# SparkFun_Polar-HeartRate.net
KiCad netlist of a schematic drawn in EAGLE
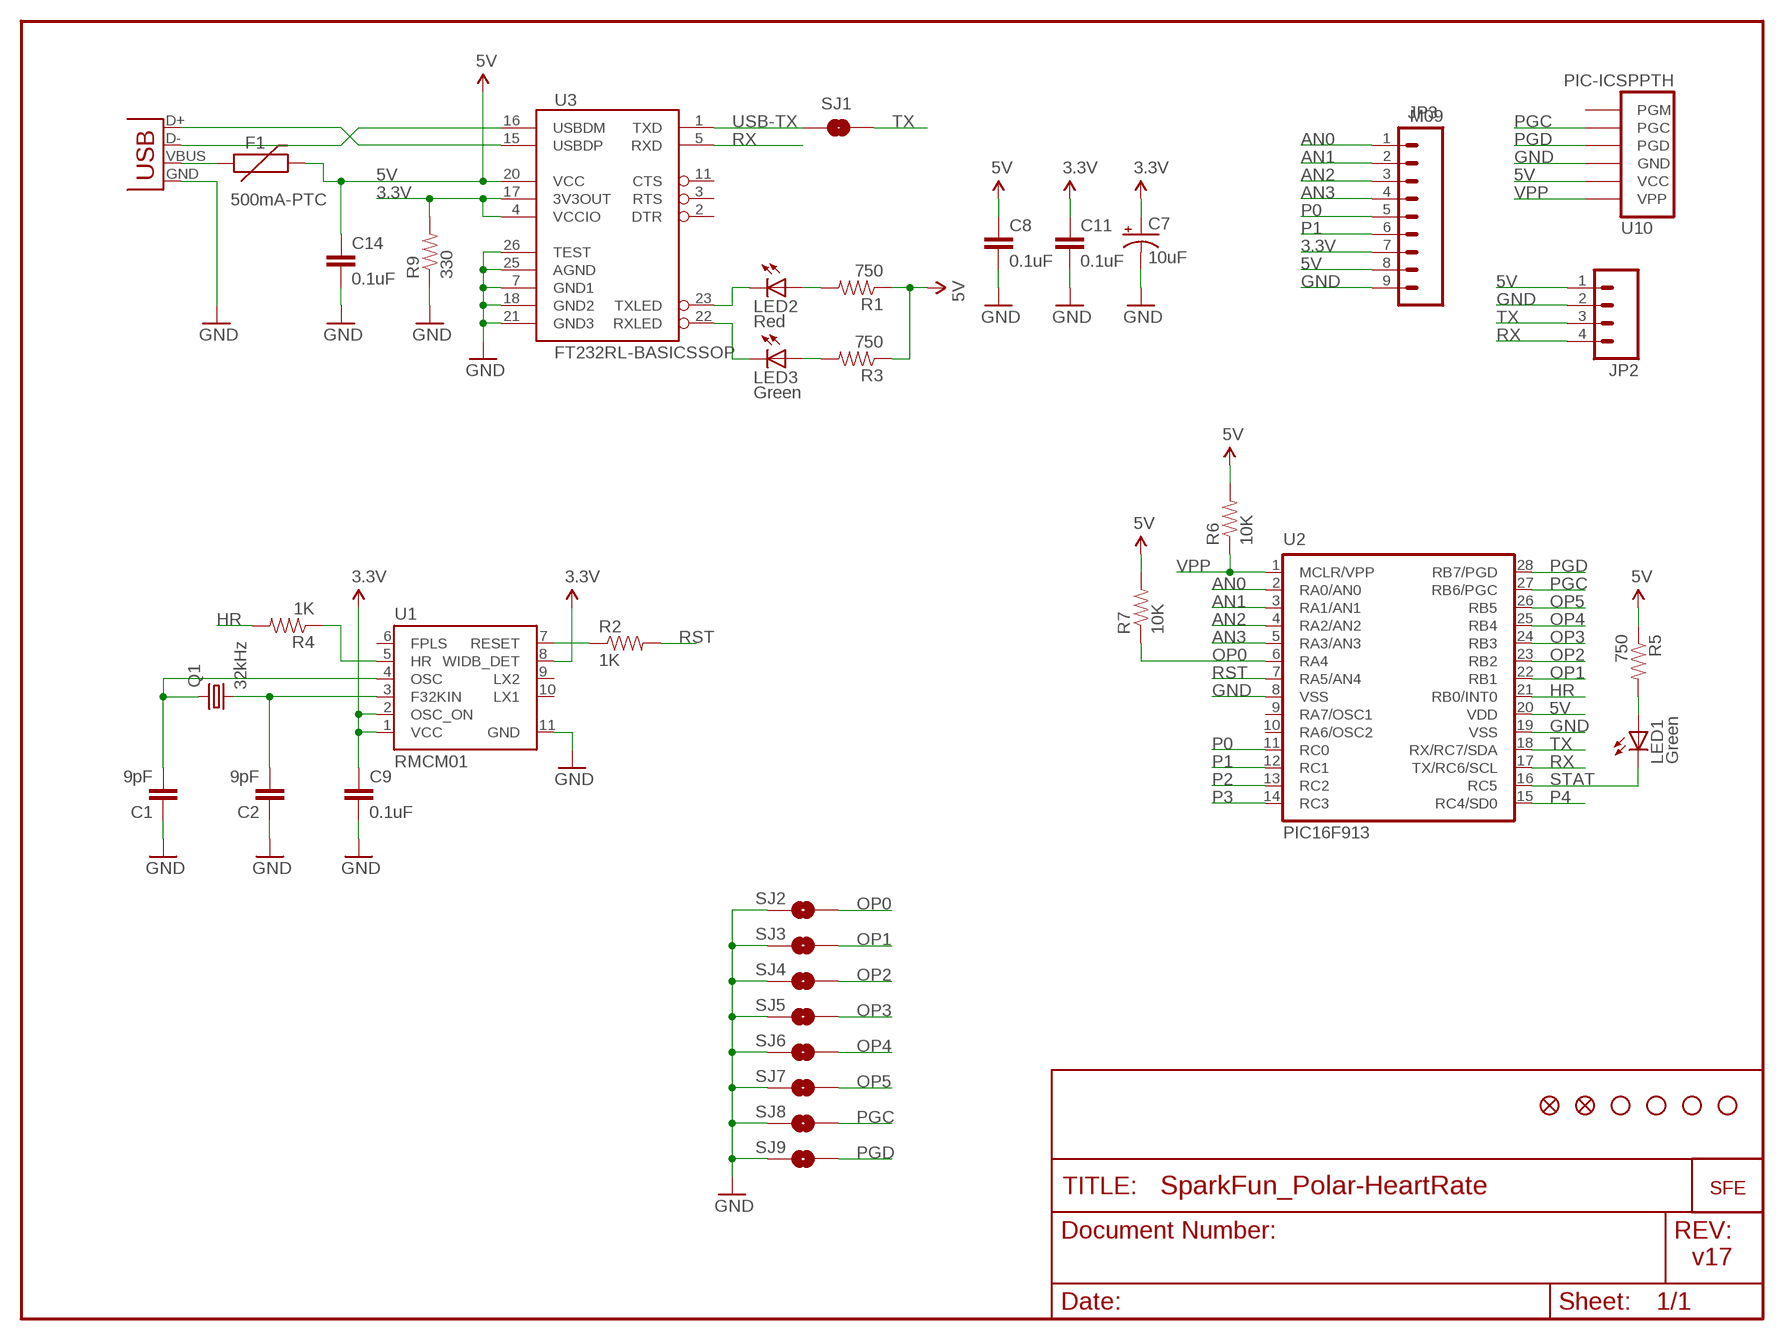
[diagram p0: schematic, sheet 1]

(export (version "E")
  (design (tool "Eeschema 10.0.6"))
  (components
    (comp (ref "C1")
      (value "9pF")
      (footprint "eagle-import:0402-CAP")
      (libsource (lib "eagle-import") (part "CAP0402-CAP"))
    )
    (comp (ref "C2")
      (value "9pF")
      (footprint "eagle-import:0402-CAP")
      (libsource (lib "eagle-import") (part "CAP0402-CAP"))
    )
    (comp (ref "C7")
      (value "10uF")
      (footprint "eagle-import:EIA3216")
      (libsource (lib "eagle-import") (part "CAP_POL1206"))
    )
    (comp (ref "C8")
      (value "0.1uF")
      (footprint "eagle-import:0402-CAP")
      (libsource (lib "eagle-import") (part "CAP0402-CAP"))
    )
    (comp (ref "C9")
      (value "0.1uF")
      (footprint "eagle-import:0402-CAP")
      (libsource (lib "eagle-import") (part "CAP0402-CAP"))
    )
    (comp (ref "C11")
      (value "0.1uF")
      (footprint "eagle-import:0402-CAP")
      (libsource (lib "eagle-import") (part "CAP0402-CAP"))
    )
    (comp (ref "C14")
      (value "0.1uF")
      (footprint "eagle-import:0402-CAP")
      (libsource (lib "eagle-import") (part "CAP0402-CAP"))
    )
    (comp (ref "F1")
      (value "500mA-PTC")
      (footprint "eagle-import:PTC-1206")
      (libsource (lib "eagle-import") (part "PTCSMD"))
    )
    (comp (ref "JP2")
      (value "M04PTH")
      (footprint "eagle-import:1X04")
      (libsource (lib "eagle-import") (part "M04PTH"))
    )
    (comp (ref "JP3")
      (value "M09")
      (footprint "eagle-import:1X09")
      (libsource (lib "eagle-import") (part "M09"))
    )
    (comp (ref "LED1")
      (value "Green")
      (footprint "eagle-import:LED-0603")
      (libsource (lib "eagle-import") (part "LED0603"))
    )
    (comp (ref "LED2")
      (value "Red")
      (footprint "eagle-import:LED-0603")
      (libsource (lib "eagle-import") (part "LED0603"))
    )
    (comp (ref "LED3")
      (value "Green")
      (footprint "eagle-import:LED-0603")
      (libsource (lib "eagle-import") (part "LED0603"))
    )
    (comp (ref "Q1")
      (value "32kHz")
      (footprint "eagle-import:CRYSTAL-32KHZ-SMD_EPSON_MC146")
      (libsource (lib "eagle-import") (part "CRYSTALEPSONMC146"))
    )
    (comp (ref "R1")
      (value "750")
      (footprint "eagle-import:0402-RES")
      (libsource (lib "eagle-import") (part "RESISTOR0402-RES"))
    )
    (comp (ref "R2")
      (value "1K")
      (footprint "eagle-import:0402-RES")
      (libsource (lib "eagle-import") (part "RESISTOR0402-RES"))
    )
    (comp (ref "R3")
      (value "750")
      (footprint "eagle-import:0402-RES")
      (libsource (lib "eagle-import") (part "RESISTOR0402-RES"))
    )
    (comp (ref "R4")
      (value "1K")
      (footprint "eagle-import:0402-RES")
      (libsource (lib "eagle-import") (part "RESISTOR0402-RES"))
    )
    (comp (ref "R5")
      (value "750")
      (footprint "eagle-import:0402-RES")
      (libsource (lib "eagle-import") (part "RESISTOR0402-RES"))
    )
    (comp (ref "R6")
      (value "10K")
      (footprint "eagle-import:0402-RES")
      (libsource (lib "eagle-import") (part "RESISTOR0402-RES"))
    )
    (comp (ref "R7")
      (value "10K")
      (footprint "eagle-import:0402-RES")
      (libsource (lib "eagle-import") (part "RESISTOR0402-RES"))
    )
    (comp (ref "R9")
      (value "330")
      (footprint "eagle-import:0402-RES")
      (libsource (lib "eagle-import") (part "RESISTOR0402-RES"))
    )
    (comp (ref "SJ1")
      (value "SOLDERJUMPERNC2")
      (footprint "eagle-import:SJ_2S-NOTRACE")
      (libsource (lib "eagle-import") (part "SOLDERJUMPERNC2"))
    )
    (comp (ref "SJ2")
      (value "SOLDERJUMPERNO")
      (footprint "eagle-import:SJ_2S-NO")
      (libsource (lib "eagle-import") (part "SOLDERJUMPERNO"))
    )
    (comp (ref "SJ3")
      (value "SOLDERJUMPERNO")
      (footprint "eagle-import:SJ_2S-NO")
      (libsource (lib "eagle-import") (part "SOLDERJUMPERNO"))
    )
    (comp (ref "SJ4")
      (value "SOLDERJUMPERNO")
      (footprint "eagle-import:SJ_2S-NO")
      (libsource (lib "eagle-import") (part "SOLDERJUMPERNO"))
    )
    (comp (ref "SJ5")
      (value "SOLDERJUMPERNO")
      (footprint "eagle-import:SJ_2S-NO")
      (libsource (lib "eagle-import") (part "SOLDERJUMPERNO"))
    )
    (comp (ref "SJ6")
      (value "SOLDERJUMPERNO")
      (footprint "eagle-import:SJ_2S-NO")
      (libsource (lib "eagle-import") (part "SOLDERJUMPERNO"))
    )
    (comp (ref "SJ7")
      (value "SOLDERJUMPERNO")
      (footprint "eagle-import:SJ_2S-NO")
      (libsource (lib "eagle-import") (part "SOLDERJUMPERNO"))
    )
    (comp (ref "SJ8")
      (value "SOLDERJUMPERNO")
      (footprint "eagle-import:SJ_2S-NO")
      (libsource (lib "eagle-import") (part "SOLDERJUMPERNO"))
    )
    (comp (ref "SJ9")
      (value "SOLDERJUMPERNO")
      (footprint "eagle-import:SJ_2S-NO")
      (libsource (lib "eagle-import") (part "SOLDERJUMPERNO"))
    )
    (comp (ref "U$1")
      (value "LOGO-SFENEW")
      (footprint "eagle-import:SFE-NEW-WEBLOGO")
      (libsource (lib "eagle-import") (part "LOGO-SFENEW"))
    )
    (comp (ref "U$4")
      (value "FIDUCIAL1X2")
      (footprint "eagle-import:FIDUCIAL-1X2")
      (libsource (lib "eagle-import") (part "FIDUCIAL1X2"))
    )
    (comp (ref "U$8")
      (value "FIDUCIAL1X2")
      (footprint "eagle-import:FIDUCIAL-1X2")
      (libsource (lib "eagle-import") (part "FIDUCIAL1X2"))
    )
    (comp (ref "U$13")
      (value "STAND-OFF")
      (footprint "eagle-import:STAND-OFF")
      (libsource (lib "eagle-import") (part "STAND-OFF"))
    )
    (comp (ref "U$15")
      (value "STAND-OFF")
      (footprint "eagle-import:STAND-OFF")
      (libsource (lib "eagle-import") (part "STAND-OFF"))
    )
    (comp (ref "U$16")
      (value "STAND-OFF")
      (footprint "eagle-import:STAND-OFF")
      (libsource (lib "eagle-import") (part "STAND-OFF"))
    )
    (comp (ref "U$17")
      (value "STAND-OFF")
      (footprint "eagle-import:STAND-OFF")
      (libsource (lib "eagle-import") (part "STAND-OFF"))
    )
    (comp (ref "U1")
      (value "RMCM01")
      (footprint "eagle-import:RMCM01")
      (libsource (lib "eagle-import") (part "RMCM01SMD"))
    )
    (comp (ref "U2")
      (value "PIC16F913")
      (footprint "eagle-import:SO-28W")
      (libsource (lib "eagle-import") (part "PIC16F913SOIC28"))
    )
    (comp (ref "U3")
      (value "FT232RL-BASICSSOP")
      (footprint "eagle-import:SSOP28DB")
      (libsource (lib "eagle-import") (part "FT232RL-BASICSSOP"))
    )
    (comp (ref "U10")
      (value "PIC-ICSPPTH")
      (footprint "eagle-import:MOLEX-1X6")
      (libsource (lib "eagle-import") (part "PIC-ICSPPTH"))
    )
    (comp (ref "X1")
      (value "USBSMD")
      (footprint "eagle-import:USB-MINIB")
      (libsource (lib "eagle-import") (part "USBSMD"))
    )
  )
  (nets
    (net (code "1") (name "/AN0") (class "Default")
      (node (ref "JP3") (pin "1") (pinfunction "1_1") (pintype "passive"))
      (node (ref "U2") (pin "2") (pinfunction "RA0/AN0_2") (pintype "bidirectional"))
    )
    (net (code "2") (name "/AN1") (class "Default")
      (node (ref "JP3") (pin "2") (pinfunction "2_2") (pintype "passive"))
      (node (ref "U2") (pin "3") (pinfunction "RA1/AN1_3") (pintype "bidirectional"))
    )
    (net (code "3") (name "/AN2") (class "Default")
      (node (ref "JP3") (pin "3") (pinfunction "3_3") (pintype "passive"))
      (node (ref "U2") (pin "4") (pinfunction "RA2/AN2_4") (pintype "bidirectional"))
    )
    (net (code "4") (name "/AN3") (class "Default")
      (node (ref "JP3") (pin "4") (pinfunction "4_4") (pintype "passive"))
      (node (ref "U2") (pin "5") (pinfunction "RA3/AN3_5") (pintype "bidirectional"))
    )
    (net (code "5") (name "/HR") (class "Default")
      (node (ref "R4") (pin "2") (pinfunction "2_2") (pintype "passive"))
      (node (ref "U2") (pin "21") (pinfunction "RB0/INT0_21") (pintype "bidirectional"))
    )
    (net (code "6") (name "/OP0") (class "Default")
      (node (ref "R7") (pin "1") (pinfunction "1_1") (pintype "passive"))
      (node (ref "SJ2") (pin "2") (pinfunction "2_2") (pintype "passive"))
      (node (ref "U2") (pin "6") (pinfunction "RA4_6") (pintype "bidirectional"))
    )
    (net (code "7") (name "/OP1") (class "Default")
      (node (ref "SJ3") (pin "2") (pinfunction "2_2") (pintype "passive"))
      (node (ref "U2") (pin "22") (pinfunction "RB1_22") (pintype "bidirectional"))
    )
    (net (code "8") (name "/OP2") (class "Default")
      (node (ref "SJ4") (pin "2") (pinfunction "2_2") (pintype "passive"))
      (node (ref "U2") (pin "23") (pinfunction "RB2_23") (pintype "bidirectional"))
    )
    (net (code "9") (name "/OP3") (class "Default")
      (node (ref "SJ5") (pin "2") (pinfunction "2_2") (pintype "passive"))
      (node (ref "U2") (pin "24") (pinfunction "RB3_24") (pintype "bidirectional"))
    )
    (net (code "10") (name "/OP4") (class "Default")
      (node (ref "SJ6") (pin "2") (pinfunction "2_2") (pintype "passive"))
      (node (ref "U2") (pin "25") (pinfunction "RB4_25") (pintype "bidirectional"))
    )
    (net (code "11") (name "/OP5") (class "Default")
      (node (ref "SJ7") (pin "2") (pinfunction "2_2") (pintype "passive"))
      (node (ref "U2") (pin "26") (pinfunction "RB5_26") (pintype "bidirectional"))
    )
    (net (code "12") (name "/P0") (class "Default")
      (node (ref "JP3") (pin "5") (pinfunction "5_5") (pintype "passive"))
      (node (ref "U2") (pin "11") (pinfunction "RC0_11") (pintype "bidirectional"))
    )
    (net (code "13") (name "/P1") (class "Default")
      (node (ref "JP3") (pin "6") (pinfunction "6_6") (pintype "passive"))
      (node (ref "U2") (pin "12") (pinfunction "RC1_12") (pintype "bidirectional"))
    )
    (net (code "14") (name "/P2") (class "Default")
      (node (ref "U2") (pin "13") (pinfunction "RC2_13") (pintype "bidirectional"))
    )
    (net (code "15") (name "/P3") (class "Default")
      (node (ref "U2") (pin "14") (pinfunction "RC3_14") (pintype "bidirectional"))
    )
    (net (code "16") (name "/P4") (class "Default")
      (node (ref "U2") (pin "15") (pinfunction "RC4/SD0_15") (pintype "bidirectional"))
    )
    (net (code "17") (name "/PGC") (class "Default")
      (node (ref "SJ8") (pin "2") (pinfunction "2_2") (pintype "passive"))
      (node (ref "U10") (pin "2") (pinfunction "PGC_2") (pintype "bidirectional"))
      (node (ref "U2") (pin "27") (pinfunction "RB6/PGC_27") (pintype "bidirectional"))
    )
    (net (code "18") (name "/PGD") (class "Default")
      (node (ref "SJ9") (pin "2") (pinfunction "2_2") (pintype "passive"))
      (node (ref "U10") (pin "3") (pinfunction "PGD_3") (pintype "bidirectional"))
      (node (ref "U2") (pin "28") (pinfunction "RB7/PGD_28") (pintype "bidirectional"))
    )
    (net (code "19") (name "/RST") (class "Default")
      (node (ref "R2") (pin "2") (pinfunction "2_2") (pintype "passive"))
      (node (ref "U2") (pin "7") (pinfunction "RA5/AN4_7") (pintype "bidirectional"))
    )
    (net (code "20") (name "/RX") (class "Default")
      (node (ref "JP2") (pin "4") (pinfunction "4_4") (pintype "passive"))
      (node (ref "U2") (pin "17") (pinfunction "TX/RC6/SCL_17") (pintype "bidirectional"))
      (node (ref "U3") (pin "5") (pinfunction "RXD_5") (pintype "input"))
    )
    (net (code "21") (name "/STAT") (class "Default")
      (node (ref "LED1") (pin "C") (pinfunction "C_C") (pintype "passive"))
      (node (ref "U2") (pin "16") (pinfunction "RC5_16") (pintype "bidirectional"))
    )
    (net (code "22") (name "/TX") (class "Default")
      (node (ref "JP2") (pin "3") (pinfunction "3_3") (pintype "passive"))
      (node (ref "SJ1") (pin "2") (pinfunction "2_2") (pintype "passive"))
      (node (ref "U2") (pin "18") (pinfunction "RX/RC7/SDA_18") (pintype "input"))
    )
    (net (code "23") (name "/USB-TX") (class "Default")
      (node (ref "SJ1") (pin "1") (pinfunction "1_1") (pintype "passive"))
      (node (ref "U3") (pin "1") (pinfunction "TXD_1") (pintype "output"))
    )
    (net (code "24") (name "/VPP") (class "Default")
      (node (ref "R6") (pin "1") (pinfunction "1_1") (pintype "passive"))
      (node (ref "U10") (pin "6") (pinfunction "VPP_6") (pintype "bidirectional"))
      (node (ref "U2") (pin "1") (pinfunction "MCLR/VPP_1") (pintype "bidirectional"))
    )
    (net (code "25") (name "3.3V") (class "Default")
      (node (ref "C11") (pin "1") (pinfunction "1_1") (pintype "passive"))
      (node (ref "C7") (pin "A") (pinfunction "+_A") (pintype "passive"))
      (node (ref "C9") (pin "1") (pinfunction "1_1") (pintype "passive"))
      (node (ref "JP3") (pin "7") (pinfunction "7_7") (pintype "passive"))
      (node (ref "R9") (pin "2") (pinfunction "2_2") (pintype "passive"))
      (node (ref "U1") (pin "1") (pinfunction "VCC_1") (pintype "bidirectional"))
      (node (ref "U1") (pin "2") (pinfunction "OSC_ON_2") (pintype "bidirectional"))
      (node (ref "U1") (pin "8") (pinfunction "WIDB_DET_8") (pintype "bidirectional"))
      (node (ref "U3") (pin "17") (pinfunction "3V3OUT_17") (pintype "output"))
      (node (ref "U3") (pin "4") (pinfunction "VCCIO_4") (pintype "power_in"))
    )
    (net (code "26") (name "5V") (class "Default")
      (node (ref "C14") (pin "1") (pinfunction "1_1") (pintype "passive"))
      (node (ref "C8") (pin "1") (pinfunction "1_1") (pintype "passive"))
      (node (ref "F1") (pin "2") (pinfunction "2_2") (pintype "bidirectional"))
      (node (ref "JP2") (pin "1") (pinfunction "1_1") (pintype "passive"))
      (node (ref "JP3") (pin "8") (pinfunction "8_8") (pintype "passive"))
      (node (ref "R1") (pin "1") (pinfunction "1_1") (pintype "passive"))
      (node (ref "R3") (pin "1") (pinfunction "1_1") (pintype "passive"))
      (node (ref "R5") (pin "1") (pinfunction "1_1") (pintype "passive"))
      (node (ref "R6") (pin "2") (pinfunction "2_2") (pintype "passive"))
      (node (ref "R7") (pin "2") (pinfunction "2_2") (pintype "passive"))
      (node (ref "U10") (pin "5") (pinfunction "VCC_5") (pintype "bidirectional"))
      (node (ref "U2") (pin "20") (pinfunction "VDD_20") (pintype "power_in"))
      (node (ref "U3") (pin "20") (pinfunction "VCC_20") (pintype "power_in"))
    )
    (net (code "27") (name "GND") (class "Default")
      (node (ref "C1") (pin "1") (pinfunction "1_1") (pintype "passive"))
      (node (ref "C11") (pin "2") (pinfunction "2_2") (pintype "passive"))
      (node (ref "C14") (pin "2") (pinfunction "2_2") (pintype "passive"))
      (node (ref "C2") (pin "1") (pinfunction "1_1") (pintype "passive"))
      (node (ref "C7") (pin "C") (pinfunction "-_C") (pintype "passive"))
      (node (ref "C8") (pin "2") (pinfunction "2_2") (pintype "passive"))
      (node (ref "C9") (pin "2") (pinfunction "2_2") (pintype "passive"))
      (node (ref "JP2") (pin "2") (pinfunction "2_2") (pintype "passive"))
      (node (ref "JP3") (pin "9") (pinfunction "9_9") (pintype "passive"))
      (node (ref "R9") (pin "1") (pinfunction "1_1") (pintype "passive"))
      (node (ref "SJ2") (pin "1") (pinfunction "1_1") (pintype "passive"))
      (node (ref "SJ3") (pin "1") (pinfunction "1_1") (pintype "passive"))
      (node (ref "SJ4") (pin "1") (pinfunction "1_1") (pintype "passive"))
      (node (ref "SJ5") (pin "1") (pinfunction "1_1") (pintype "passive"))
      (node (ref "SJ6") (pin "1") (pinfunction "1_1") (pintype "passive"))
      (node (ref "SJ7") (pin "1") (pinfunction "1_1") (pintype "passive"))
      (node (ref "SJ8") (pin "1") (pinfunction "1_1") (pintype "passive"))
      (node (ref "SJ9") (pin "1") (pinfunction "1_1") (pintype "passive"))
      (node (ref "U1") (pin "11") (pinfunction "GND_11") (pintype "bidirectional"))
      (node (ref "U10") (pin "4") (pinfunction "GND_4") (pintype "bidirectional"))
      (node (ref "U2") (pin "19") (pinfunction "VSS_19") (pintype "power_in"))
      (node (ref "U2") (pin "8") (pinfunction "VSS_8") (pintype "power_in"))
      (node (ref "U3") (pin "18") (pinfunction "GND2_18") (pintype "power_in"))
      (node (ref "U3") (pin "21") (pinfunction "GND3_21") (pintype "power_in"))
      (node (ref "U3") (pin "25") (pinfunction "AGND_25") (pintype "power_in"))
      (node (ref "U3") (pin "26") (pinfunction "TEST_26") (pintype "input"))
      (node (ref "U3") (pin "7") (pinfunction "GND1_7") (pintype "power_in"))
      (node (ref "X1") (pin "GND") (pinfunction "GND_GND") (pintype "bidirectional"))
    )
    (net (code "28") (name "Net-(F1-Pad1)") (class "Default")
      (node (ref "F1") (pin "1") (pinfunction "1_1") (pintype "bidirectional"))
      (node (ref "X1") (pin "VBUS") (pinfunction "VBUS_VBUS") (pintype "bidirectional"))
    )
    (net (code "29") (name "Net-(LED1-PadA)") (class "Default")
      (node (ref "LED1") (pin "A") (pinfunction "A_A") (pintype "passive"))
      (node (ref "R5") (pin "2") (pinfunction "2_2") (pintype "passive"))
    )
    (net (code "30") (name "Net-(LED2-PadA)") (class "Default")
      (node (ref "LED2") (pin "A") (pinfunction "A_A") (pintype "passive"))
      (node (ref "R1") (pin "2") (pinfunction "2_2") (pintype "passive"))
    )
    (net (code "31") (name "Net-(LED3-PadA)") (class "Default")
      (node (ref "LED3") (pin "A") (pinfunction "A_A") (pintype "passive"))
      (node (ref "R3") (pin "2") (pinfunction "2_2") (pintype "passive"))
    )
    (net (code "32") (name "Net-(Q1-1)") (class "Default")
      (node (ref "C2") (pin "2") (pinfunction "2_2") (pintype "passive"))
      (node (ref "Q1") (pin "P$2") (pinfunction "1_P$2") (pintype "passive"))
      (node (ref "U1") (pin "3") (pinfunction "F32KIN_3") (pintype "bidirectional"))
    )
    (net (code "33") (name "Net-(Q1-2)") (class "Default")
      (node (ref "C1") (pin "2") (pinfunction "2_2") (pintype "passive"))
      (node (ref "Q1") (pin "P$1") (pinfunction "2_P$1") (pintype "passive"))
      (node (ref "U1") (pin "4") (pinfunction "OSC_4") (pintype "bidirectional"))
    )
    (net (code "34") (name "Net-(U1-HR)") (class "Default")
      (node (ref "R4") (pin "1") (pinfunction "1_1") (pintype "passive"))
      (node (ref "U1") (pin "5") (pinfunction "HR_5") (pintype "bidirectional"))
    )
    (net (code "35") (name "Net-(U1-RESET)") (class "Default")
      (node (ref "R2") (pin "1") (pinfunction "1_1") (pintype "passive"))
      (node (ref "U1") (pin "7") (pinfunction "RESET_7") (pintype "bidirectional"))
    )
    (net (code "36") (name "Net-(U3-RXLED)") (class "Default")
      (node (ref "LED3") (pin "C") (pinfunction "C_C") (pintype "passive"))
      (node (ref "U3") (pin "22") (pinfunction "RXLED_22") (pintype "bidirectional"))
    )
    (net (code "37") (name "Net-(U3-TXLED)") (class "Default")
      (node (ref "LED2") (pin "C") (pinfunction "C_C") (pintype "passive"))
      (node (ref "U3") (pin "23") (pinfunction "TXLED_23") (pintype "bidirectional"))
    )
    (net (code "38") (name "Net-(U3-USBDM)") (class "Default")
      (node (ref "U3") (pin "16") (pinfunction "USBDM_16") (pintype "bidirectional"))
      (node (ref "X1") (pin "D-") (pinfunction "D-_D-") (pintype "bidirectional"))
    )
    (net (code "39") (name "Net-(U3-USBDP)") (class "Default")
      (node (ref "U3") (pin "15") (pinfunction "USBDP_15") (pintype "bidirectional"))
      (node (ref "X1") (pin "D+") (pinfunction "D+_D+") (pintype "bidirectional"))
    )
    (net (code "40") (name "unconnected-(U1-FPLS-Pad6)") (class "Default")
      (node (ref "U1") (pin "6") (pinfunction "FPLS_6") (pintype "bidirectional"))
    )
    (net (code "41") (name "unconnected-(U1-LX1-Pad10)") (class "Default")
      (node (ref "U1") (pin "10") (pinfunction "LX1_10") (pintype "bidirectional"))
    )
    (net (code "42") (name "unconnected-(U1-LX2-Pad9)") (class "Default")
      (node (ref "U1") (pin "9") (pinfunction "LX2_9") (pintype "bidirectional"))
    )
    (net (code "43") (name "unconnected-(U2-RA6{slash}OSC2-Pad10)") (class "Default")
      (node (ref "U2") (pin "10") (pinfunction "RA6/OSC2_10") (pintype "bidirectional"))
    )
    (net (code "44") (name "unconnected-(U2-RA7{slash}OSC1-Pad9)") (class "Default")
      (node (ref "U2") (pin "9") (pinfunction "RA7/OSC1_9") (pintype "bidirectional"))
    )
    (net (code "45") (name "unconnected-(U3-CTS-Pad11)") (class "Default")
      (node (ref "U3") (pin "11") (pinfunction "CTS_11") (pintype "bidirectional"))
    )
    (net (code "46") (name "unconnected-(U3-DTR-Pad2)") (class "Default")
      (node (ref "U3") (pin "2") (pinfunction "DTR_2") (pintype "bidirectional"))
    )
    (net (code "47") (name "unconnected-(U3-RTS-Pad3)") (class "Default")
      (node (ref "U3") (pin "3") (pinfunction "RTS_3") (pintype "bidirectional"))
    )
    (net (code "48") (name "unconnected-(U10-PGM-Pad1)") (class "Default")
      (node (ref "U10") (pin "1") (pinfunction "PGM_1") (pintype "bidirectional"))
    )
  )
)
